# Modulo_shield_L6470-36.net
KiCad netlist of a schematic drawn in EAGLE
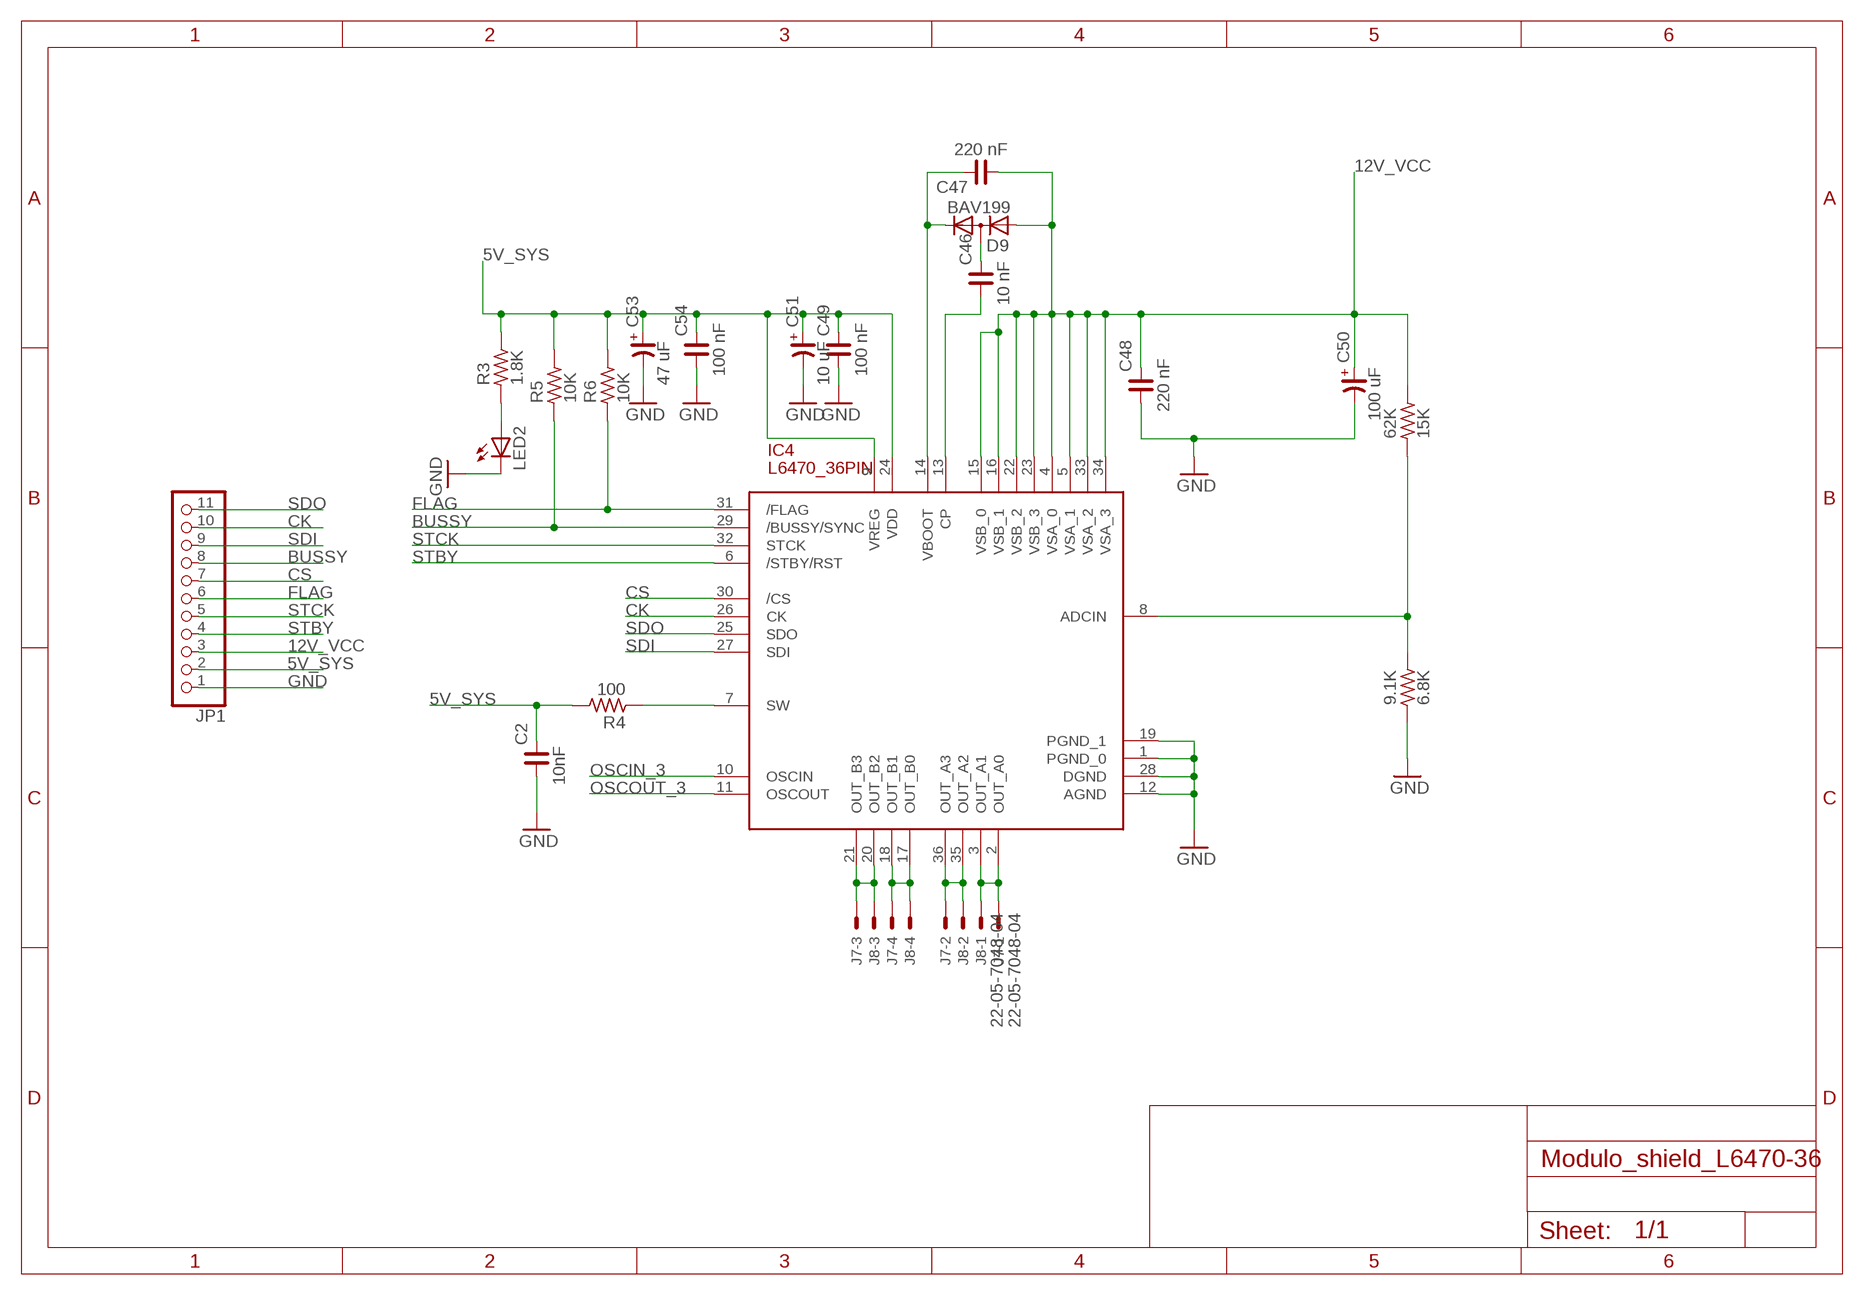
[diagram p0: schematic, sheet 1]

(export (version "E")
  (design (tool "Eeschema 10.0.6"))
  (components
    (comp (ref "9.1K")
      (value "6.8K")
      (footprint "eagle-import:R1206")
      (libsource (lib "eagle-import") (part "R_1206"))
    )
    (comp (ref "62K")
      (value "15K")
      (footprint "eagle-import:R1206")
      (libsource (lib "eagle-import") (part "R_1206"))
    )
    (comp (ref "C2")
      (value "10nF")
      (footprint "eagle-import:C1206")
      (libsource (lib "eagle-import") (part "C_1206"))
    )
    (comp (ref "C46")
      (value "10 nF")
      (footprint "eagle-import:C1206")
      (libsource (lib "eagle-import") (part "C_1206"))
    )
    (comp (ref "C47")
      (value "220 nF")
      (footprint "eagle-import:C1206")
      (libsource (lib "eagle-import") (part "C_1206"))
    )
    (comp (ref "C48")
      (value "220 nF")
      (footprint "eagle-import:C1206")
      (libsource (lib "eagle-import") (part "C_1206"))
    )
    (comp (ref "C49")
      (value "100 nF")
      (footprint "eagle-import:C1206")
      (libsource (lib "eagle-import") (part "C_1206"))
    )
    (comp (ref "C50")
      (value "100 uF")
      (footprint "eagle-import:CSV-D")
      (libsource (lib "eagle-import") (part "CP_SV-D"))
    )
    (comp (ref "C51")
      (value "10 uF")
      (footprint "eagle-import:CSV-B")
      (libsource (lib "eagle-import") (part "CP_SV-B"))
    )
    (comp (ref "C53")
      (value "47 uF")
      (footprint "eagle-import:CSV-B")
      (libsource (lib "eagle-import") (part "CP_SV-B"))
    )
    (comp (ref "C54")
      (value "100 nF")
      (footprint "eagle-import:C1206")
      (libsource (lib "eagle-import") (part "C_1206"))
    )
    (comp (ref "D9")
      (value "BAV199")
      (footprint "eagle-import:SOT23")
      (libsource (lib "eagle-import") (part "BAV199"))
    )
    (comp (ref "IC4")
      (value "L6470_36PIN")
      (footprint "eagle-import:L6470_36PIN")
      (libsource (lib "eagle-import") (part "L6470_36PIN"))
    )
    (comp (ref "J7")
      (value "22-05-7048-04")
      (footprint "eagle-import:7395-04")
      (libsource (lib "eagle-import") (part "22-?-0405-7048"))
    )
    (comp (ref "J8")
      (value "22-05-7048-04")
      (footprint "eagle-import:7395-04")
      (libsource (lib "eagle-import") (part "22-?-0405-7048"))
    )
    (comp (ref "JP1")
      (value "PINHD-1X11/90")
      (footprint "eagle-import:1X11_90")
      (libsource (lib "eagle-import") (part "PINHD-1X11/90"))
    )
    (comp (ref "LED2")
      (value "LEDCHIPLED_1206")
      (footprint "eagle-import:CHIPLED_1206")
      (libsource (lib "eagle-import") (part "LEDCHIPLED_1206"))
    )
    (comp (ref "R3")
      (value "1.8K")
      (footprint "eagle-import:R1206")
      (libsource (lib "eagle-import") (part "R_1206"))
    )
    (comp (ref "R4")
      (value "100")
      (footprint "eagle-import:R1206")
      (libsource (lib "eagle-import") (part "R_1206"))
    )
    (comp (ref "R5")
      (value "10K")
      (footprint "eagle-import:R1206")
      (libsource (lib "eagle-import") (part "R_1206"))
    )
    (comp (ref "R6")
      (value "10K")
      (footprint "eagle-import:R1206")
      (libsource (lib "eagle-import") (part "R_1206"))
    )
  )
  (nets
    (net (code "1") (name "/5V_SYS") (class "Default")
      (node (ref "C2") (pin "2") (pinfunction "2_2") (pintype "passive"))
      (node (ref "C49") (pin "2") (pinfunction "2_2") (pintype "passive"))
      (node (ref "C51") (pin "+") (pinfunction "+_+") (pintype "passive"))
      (node (ref "C53") (pin "+") (pinfunction "+_+") (pintype "passive"))
      (node (ref "C54") (pin "2") (pinfunction "2_2") (pintype "passive"))
      (node (ref "IC4") (pin "24") (pinfunction "VDD_24") (pintype "bidirectional"))
      (node (ref "IC4") (pin "9") (pinfunction "VREG_9") (pintype "bidirectional"))
      (node (ref "JP1") (pin "2") (pinfunction "2_2") (pintype "passive"))
      (node (ref "R3") (pin "2") (pinfunction "2_2") (pintype "passive"))
      (node (ref "R4") (pin "2") (pinfunction "2_2") (pintype "passive"))
      (node (ref "R5") (pin "2") (pinfunction "2_2") (pintype "passive"))
      (node (ref "R6") (pin "2") (pinfunction "2_2") (pintype "passive"))
    )
    (net (code "2") (name "/12V_VCC") (class "Default")
      (node (ref "62K") (pin "2") (pinfunction "2_2") (pintype "passive"))
      (node (ref "C47") (pin "1") (pinfunction "1_1") (pintype "passive"))
      (node (ref "C48") (pin "2") (pinfunction "2_2") (pintype "passive"))
      (node (ref "C50") (pin "+") (pinfunction "+_+") (pintype "passive"))
      (node (ref "D9") (pin "1") (pinfunction "A_1") (pintype "passive"))
      (node (ref "IC4") (pin "15") (pinfunction "VSB_0_15") (pintype "bidirectional"))
      (node (ref "IC4") (pin "16") (pinfunction "VSB_1_16") (pintype "bidirectional"))
      (node (ref "IC4") (pin "22") (pinfunction "VSB_2_22") (pintype "bidirectional"))
      (node (ref "IC4") (pin "23") (pinfunction "VSB_3_23") (pintype "bidirectional"))
      (node (ref "IC4") (pin "33") (pinfunction "VSA_2_33") (pintype "bidirectional"))
      (node (ref "IC4") (pin "34") (pinfunction "VSA_3_34") (pintype "bidirectional"))
      (node (ref "IC4") (pin "4") (pinfunction "VSA_0_4") (pintype "bidirectional"))
      (node (ref "IC4") (pin "5") (pinfunction "VSA_1_5") (pintype "bidirectional"))
      (node (ref "JP1") (pin "3") (pinfunction "3_3") (pintype "passive"))
    )
    (net (code "3") (name "/BUSSY") (class "Default")
      (node (ref "IC4") (pin "29") (pinfunction "/BUSSY/SYNC_29") (pintype "bidirectional"))
      (node (ref "JP1") (pin "8") (pinfunction "8_8") (pintype "passive"))
      (node (ref "R5") (pin "1") (pinfunction "1_1") (pintype "passive"))
    )
    (net (code "4") (name "/CK") (class "Default")
      (node (ref "IC4") (pin "26") (pinfunction "CK_26") (pintype "bidirectional"))
      (node (ref "JP1") (pin "10") (pinfunction "10_10") (pintype "passive"))
    )
    (net (code "5") (name "/CS") (class "Default")
      (node (ref "IC4") (pin "30") (pinfunction "/CS_30") (pintype "bidirectional"))
      (node (ref "JP1") (pin "7") (pinfunction "7_7") (pintype "passive"))
    )
    (net (code "6") (name "/FLAG") (class "Default")
      (node (ref "IC4") (pin "31") (pinfunction "/FLAG_31") (pintype "bidirectional"))
      (node (ref "JP1") (pin "6") (pinfunction "6_6") (pintype "passive"))
      (node (ref "R6") (pin "1") (pinfunction "1_1") (pintype "passive"))
    )
    (net (code "7") (name "/OSCIN_3") (class "Default")
      (node (ref "IC4") (pin "10") (pinfunction "OSCIN_10") (pintype "bidirectional"))
    )
    (net (code "8") (name "/OSCOUT_3") (class "Default")
      (node (ref "IC4") (pin "11") (pinfunction "OSCOUT_11") (pintype "bidirectional"))
    )
    (net (code "9") (name "/SDI") (class "Default")
      (node (ref "IC4") (pin "27") (pinfunction "SDI_27") (pintype "bidirectional"))
      (node (ref "JP1") (pin "9") (pinfunction "9_9") (pintype "passive"))
    )
    (net (code "10") (name "/SDO") (class "Default")
      (node (ref "IC4") (pin "25") (pinfunction "SDO_25") (pintype "bidirectional"))
      (node (ref "JP1") (pin "11") (pinfunction "11_11") (pintype "passive"))
    )
    (net (code "11") (name "/STBY") (class "Default")
      (node (ref "IC4") (pin "6") (pinfunction "/STBY/RST_6") (pintype "bidirectional"))
      (node (ref "JP1") (pin "4") (pinfunction "4_4") (pintype "passive"))
    )
    (net (code "12") (name "/STCK") (class "Default")
      (node (ref "IC4") (pin "32") (pinfunction "STCK_32") (pintype "bidirectional"))
      (node (ref "JP1") (pin "5") (pinfunction "5_5") (pintype "passive"))
    )
    (net (code "13") (name "GND") (class "Default")
      (node (ref "9.1K") (pin "1") (pinfunction "1_1") (pintype "passive"))
      (node (ref "C2") (pin "1") (pinfunction "1_1") (pintype "passive"))
      (node (ref "C48") (pin "1") (pinfunction "1_1") (pintype "passive"))
      (node (ref "C49") (pin "1") (pinfunction "1_1") (pintype "passive"))
      (node (ref "C50") (pin "-") (pinfunction "-_-") (pintype "passive"))
      (node (ref "C51") (pin "-") (pinfunction "-_-") (pintype "passive"))
      (node (ref "C53") (pin "-") (pinfunction "-_-") (pintype "passive"))
      (node (ref "C54") (pin "1") (pinfunction "1_1") (pintype "passive"))
      (node (ref "IC4") (pin "1") (pinfunction "PGND_0_1") (pintype "bidirectional"))
      (node (ref "IC4") (pin "12") (pinfunction "AGND_12") (pintype "bidirectional"))
      (node (ref "IC4") (pin "19") (pinfunction "PGND_1_19") (pintype "bidirectional"))
      (node (ref "IC4") (pin "28") (pinfunction "DGND_28") (pintype "bidirectional"))
      (node (ref "JP1") (pin "1") (pinfunction "1_1") (pintype "passive"))
      (node (ref "LED2") (pin "C") (pinfunction "C_C") (pintype "passive"))
    )
    (net (code "14") (name "Net-(D9-AC)") (class "Default")
      (node (ref "C46") (pin "2") (pinfunction "2_2") (pintype "passive"))
      (node (ref "D9") (pin "3") (pinfunction "AC_3") (pintype "passive"))
    )
    (net (code "15") (name "Net-(D9-C)") (class "Default")
      (node (ref "C47") (pin "2") (pinfunction "2_2") (pintype "passive"))
      (node (ref "D9") (pin "2") (pinfunction "C_2") (pintype "passive"))
      (node (ref "IC4") (pin "14") (pinfunction "VBOOT_14") (pintype "bidirectional"))
    )
    (net (code "16") (name "Net-(IC4-ADCIN)") (class "Default")
      (node (ref "62K") (pin "1") (pinfunction "1_1") (pintype "passive"))
      (node (ref "9.1K") (pin "2") (pinfunction "2_2") (pintype "passive"))
      (node (ref "IC4") (pin "8") (pinfunction "ADCIN_8") (pintype "bidirectional"))
    )
    (net (code "17") (name "Net-(IC4-CP)") (class "Default")
      (node (ref "C46") (pin "1") (pinfunction "1_1") (pintype "passive"))
      (node (ref "IC4") (pin "13") (pinfunction "CP_13") (pintype "bidirectional"))
    )
    (net (code "18") (name "Net-(IC4-OUT_A0)") (class "Default")
      (node (ref "IC4") (pin "2") (pinfunction "OUT_A0_2") (pintype "bidirectional"))
      (node (ref "IC4") (pin "3") (pinfunction "OUT_A1_3") (pintype "bidirectional"))
      (node (ref "J7") (pin "1") (pinfunction "S_1") (pintype "passive"))
      (node (ref "J8") (pin "1") (pinfunction "S_1") (pintype "passive"))
    )
    (net (code "19") (name "Net-(IC4-OUT_A2)") (class "Default")
      (node (ref "IC4") (pin "35") (pinfunction "OUT_A2_35") (pintype "bidirectional"))
      (node (ref "IC4") (pin "36") (pinfunction "OUT_A3_36") (pintype "bidirectional"))
      (node (ref "J7") (pin "2") (pinfunction "S_2") (pintype "passive"))
      (node (ref "J8") (pin "2") (pinfunction "S_2") (pintype "passive"))
    )
    (net (code "20") (name "Net-(IC4-OUT_B0)") (class "Default")
      (node (ref "IC4") (pin "17") (pinfunction "OUT_B0_17") (pintype "bidirectional"))
      (node (ref "IC4") (pin "18") (pinfunction "OUT_B1_18") (pintype "bidirectional"))
      (node (ref "J7") (pin "4") (pinfunction "S_4") (pintype "passive"))
      (node (ref "J8") (pin "4") (pinfunction "S_4") (pintype "passive"))
    )
    (net (code "21") (name "Net-(IC4-OUT_B2)") (class "Default")
      (node (ref "IC4") (pin "20") (pinfunction "OUT_B2_20") (pintype "bidirectional"))
      (node (ref "IC4") (pin "21") (pinfunction "OUT_B3_21") (pintype "bidirectional"))
      (node (ref "J7") (pin "3") (pinfunction "S_3") (pintype "passive"))
      (node (ref "J8") (pin "3") (pinfunction "S_3") (pintype "passive"))
    )
    (net (code "22") (name "Net-(IC4-SW)") (class "Default")
      (node (ref "IC4") (pin "7") (pinfunction "SW_7") (pintype "bidirectional"))
      (node (ref "R4") (pin "1") (pinfunction "1_1") (pintype "passive"))
    )
    (net (code "23") (name "Net-(LED2-PadA)") (class "Default")
      (node (ref "LED2") (pin "A") (pinfunction "A_A") (pintype "passive"))
      (node (ref "R3") (pin "1") (pinfunction "1_1") (pintype "passive"))
    )
  )
)
